# main.net
KiCad netlist of a schematic drawn in Altium Designer
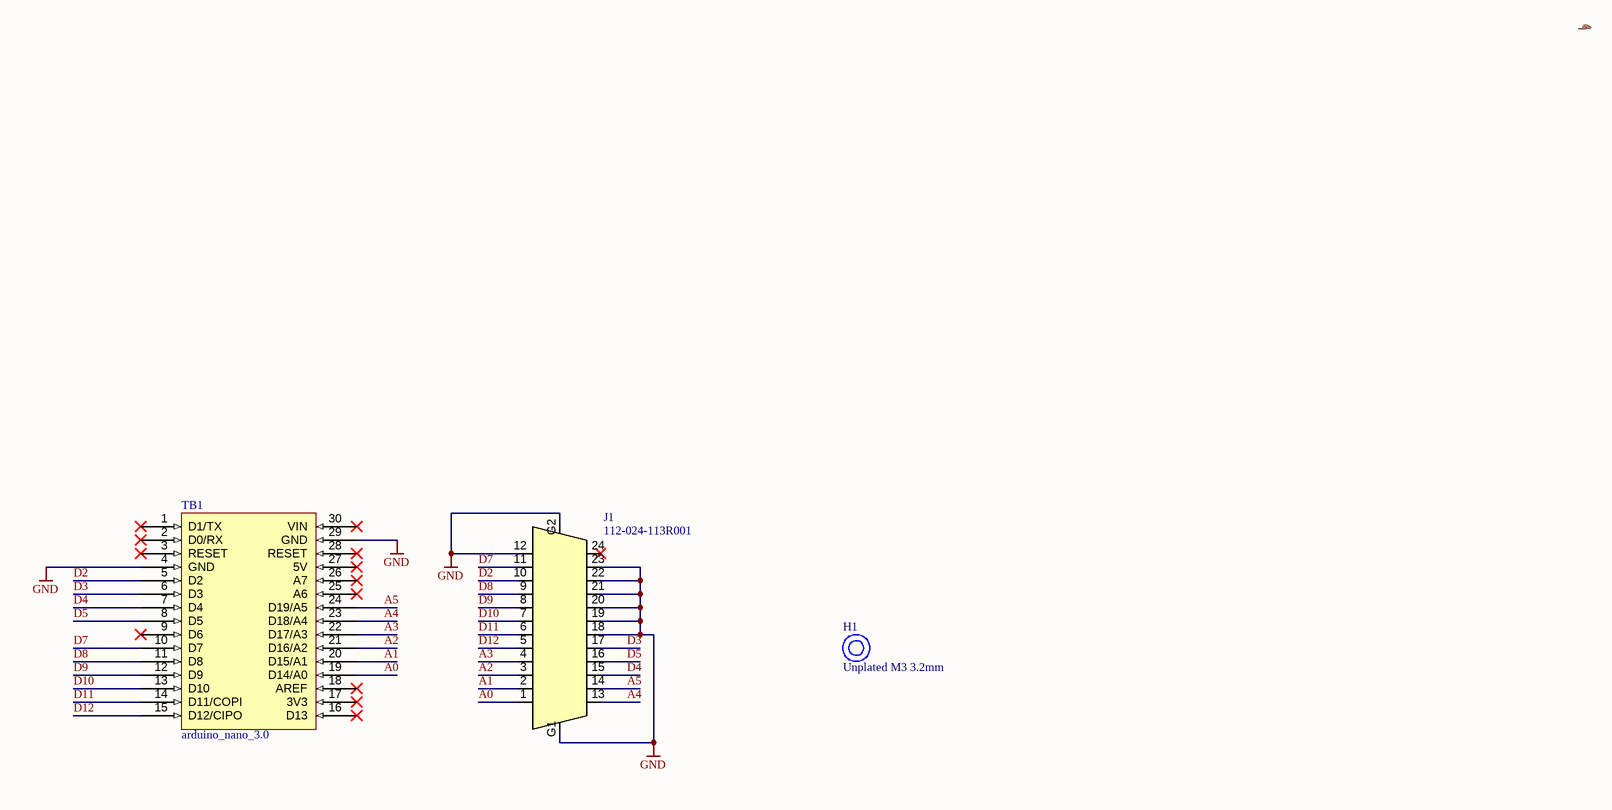
[diagram p0: main.SchDoc]

(export (version "E")
  (design (tool "Eeschema 10.0.6"))
  (components
    (comp (ref "H1")
      (value "Unplated M3 3.2mm")
      (footprint "MountingHole_3.2mm_M3_NPTH")
      (libsource (lib "jlofw") (part "mounting_hole_no_pad"))
    )
    (comp (ref "J1")
      (value "NorComp_112-024-113R001")
      (footprint "NorComp_112-024-113R001")
      (description "I/O-kontaktdon 24P Centronics male R/A dip solder")
      (fields (field (name "MANUFACTURER A P/N") "112-024-113R001"))
      (libsource (lib "jlofw") (part "NorComp_112-024-113R001"))
    )
    (comp (ref "logo1") (value "beaver") (footprint "beaver") (libsource (lib "jlofw") (part "beaver")))
    (comp (ref "TB1")
      (value "arduino_nano_3.0")
      (footprint "arduino_nano")
      (description "Arduino Nano 3.0")
      (libsource (lib "jlofw") (part "arduino_nano_3.0"))
    )
  )
  (nets
    (net (code "1") (name "/A0") (class "Default")
      (node (ref "J1") (pin "1") (pinfunction "1_1") (pintype "passive"))
      (node (ref "TB1") (pin "19") (pinfunction "D14/A0_19") (pintype "input"))
    )
    (net (code "2") (name "/A1") (class "Default")
      (node (ref "J1") (pin "2") (pinfunction "2_2") (pintype "passive"))
      (node (ref "TB1") (pin "20") (pinfunction "D15/A1_20") (pintype "input"))
    )
    (net (code "3") (name "/A2") (class "Default")
      (node (ref "J1") (pin "3") (pinfunction "3_3") (pintype "passive"))
      (node (ref "TB1") (pin "21") (pinfunction "D16/A2_21") (pintype "input"))
    )
    (net (code "4") (name "/A3") (class "Default")
      (node (ref "J1") (pin "4") (pinfunction "4_4") (pintype "passive"))
      (node (ref "TB1") (pin "22") (pinfunction "D17/A3_22") (pintype "input"))
    )
    (net (code "5") (name "/A4") (class "Default")
      (node (ref "J1") (pin "13") (pinfunction "13_13") (pintype "passive"))
      (node (ref "TB1") (pin "23") (pinfunction "D18/A4_23") (pintype "input"))
    )
    (net (code "6") (name "/A5") (class "Default")
      (node (ref "J1") (pin "14") (pinfunction "14_14") (pintype "passive"))
      (node (ref "TB1") (pin "24") (pinfunction "D19/A5_24") (pintype "input"))
    )
    (net (code "7") (name "/D2") (class "Default")
      (node (ref "J1") (pin "10") (pinfunction "10_10") (pintype "passive"))
      (node (ref "TB1") (pin "5") (pinfunction "D2_5") (pintype "input"))
    )
    (net (code "8") (name "/D3") (class "Default")
      (node (ref "J1") (pin "17") (pinfunction "17_17") (pintype "passive"))
      (node (ref "TB1") (pin "6") (pinfunction "D3_6") (pintype "input"))
    )
    (net (code "9") (name "/D4") (class "Default")
      (node (ref "J1") (pin "15") (pinfunction "15_15") (pintype "passive"))
      (node (ref "TB1") (pin "7") (pinfunction "D4_7") (pintype "input"))
    )
    (net (code "10") (name "/D5") (class "Default")
      (node (ref "J1") (pin "16") (pinfunction "16_16") (pintype "passive"))
      (node (ref "TB1") (pin "8") (pinfunction "D5_8") (pintype "input"))
    )
    (net (code "11") (name "/D7") (class "Default")
      (node (ref "J1") (pin "11") (pinfunction "11_11") (pintype "passive"))
      (node (ref "TB1") (pin "10") (pinfunction "D7_10") (pintype "input"))
    )
    (net (code "12") (name "/D8") (class "Default")
      (node (ref "J1") (pin "9") (pinfunction "9_9") (pintype "passive"))
      (node (ref "TB1") (pin "11") (pinfunction "D8_11") (pintype "input"))
    )
    (net (code "13") (name "/D9") (class "Default")
      (node (ref "J1") (pin "8") (pinfunction "8_8") (pintype "passive"))
      (node (ref "TB1") (pin "12") (pinfunction "D9_12") (pintype "input"))
    )
    (net (code "14") (name "/D10") (class "Default")
      (node (ref "J1") (pin "7") (pinfunction "7_7") (pintype "passive"))
      (node (ref "TB1") (pin "13") (pinfunction "D10_13") (pintype "input"))
    )
    (net (code "15") (name "/D11") (class "Default")
      (node (ref "J1") (pin "6") (pinfunction "6_6") (pintype "passive"))
      (node (ref "TB1") (pin "14") (pinfunction "D11/COPI_14") (pintype "input"))
    )
    (net (code "16") (name "/D12") (class "Default")
      (node (ref "J1") (pin "5") (pinfunction "5_5") (pintype "passive"))
      (node (ref "TB1") (pin "15") (pinfunction "D12/CIPO_15") (pintype "input"))
    )
    (net (code "17") (name "GND") (class "Default")
      (node (ref "J1") (pin "12") (pinfunction "12_12") (pintype "passive"))
      (node (ref "J1") (pin "18") (pinfunction "18_18") (pintype "passive"))
      (node (ref "J1") (pin "19") (pinfunction "119_19") (pintype "passive"))
      (node (ref "J1") (pin "20") (pinfunction "20_20") (pintype "passive"))
      (node (ref "J1") (pin "21") (pinfunction "21_21") (pintype "passive"))
      (node (ref "J1") (pin "22") (pinfunction "22_22") (pintype "passive"))
      (node (ref "J1") (pin "23") (pinfunction "23_23") (pintype "passive"))
      (node (ref "J1") (pin "G1") (pinfunction "G1_G1") (pintype "passive"))
      (node (ref "J1") (pin "G2") (pinfunction "G2_G2") (pintype "passive"))
      (node (ref "TB1") (pin "29") (pinfunction "GND_29") (pintype "input"))
      (node (ref "TB1") (pin "4") (pinfunction "GND_4") (pintype "input"))
    )
    (net (code "18") (name "unconnected-(J1-Pad24)") (class "Default")
      (node (ref "J1") (pin "24") (pinfunction "24_24") (pintype "passive+no_connect"))
    )
    (net (code "19") (name "unconnected-(TB1-3V3-Pad17)") (class "Default")
      (node (ref "TB1") (pin "17") (pinfunction "3V3_17") (pintype "input+no_connect"))
    )
    (net (code "20") (name "unconnected-(TB1-5V-Pad27)") (class "Default")
      (node (ref "TB1") (pin "27") (pinfunction "5V_27") (pintype "input+no_connect"))
    )
    (net (code "21") (name "unconnected-(TB1-A6-Pad25)") (class "Default")
      (node (ref "TB1") (pin "25") (pinfunction "A6_25") (pintype "input+no_connect"))
    )
    (net (code "22") (name "unconnected-(TB1-A7-Pad26)") (class "Default")
      (node (ref "TB1") (pin "26") (pinfunction "A7_26") (pintype "input+no_connect"))
    )
    (net (code "23") (name "unconnected-(TB1-AREF-Pad18)") (class "Default")
      (node (ref "TB1") (pin "18") (pinfunction "AREF_18") (pintype "input+no_connect"))
    )
    (net (code "24") (name "unconnected-(TB1-D0{slash}RX-Pad2)") (class "Default")
      (node (ref "TB1") (pin "2") (pinfunction "D0/RX_2") (pintype "input+no_connect"))
    )
    (net (code "25") (name "unconnected-(TB1-D1{slash}TX-Pad1)") (class "Default")
      (node (ref "TB1") (pin "1") (pinfunction "D1/TX_1") (pintype "input+no_connect"))
    )
    (net (code "26") (name "unconnected-(TB1-D6-Pad9)") (class "Default")
      (node (ref "TB1") (pin "9") (pinfunction "D6_9") (pintype "input+no_connect"))
    )
    (net (code "27") (name "unconnected-(TB1-D13-Pad16)") (class "Default")
      (node (ref "TB1") (pin "16") (pinfunction "D13_16") (pintype "input+no_connect"))
    )
    (net (code "28") (name "unconnected-(TB1-RESET-Pad3)") (class "Default")
      (node (ref "TB1") (pin "3") (pinfunction "RESET_3") (pintype "input+no_connect"))
    )
    (net (code "29") (name "unconnected-(TB1-RESET-Pad28)") (class "Default")
      (node (ref "TB1") (pin "28") (pinfunction "RESET_28") (pintype "input+no_connect"))
    )
    (net (code "30") (name "unconnected-(TB1-VIN-Pad30)") (class "Default")
      (node (ref "TB1") (pin "30") (pinfunction "VIN_30") (pintype "input+no_connect"))
    )
  )
)
